# Amplifier_1.net
KiCad netlist of a schematic drawn in Altium Designer
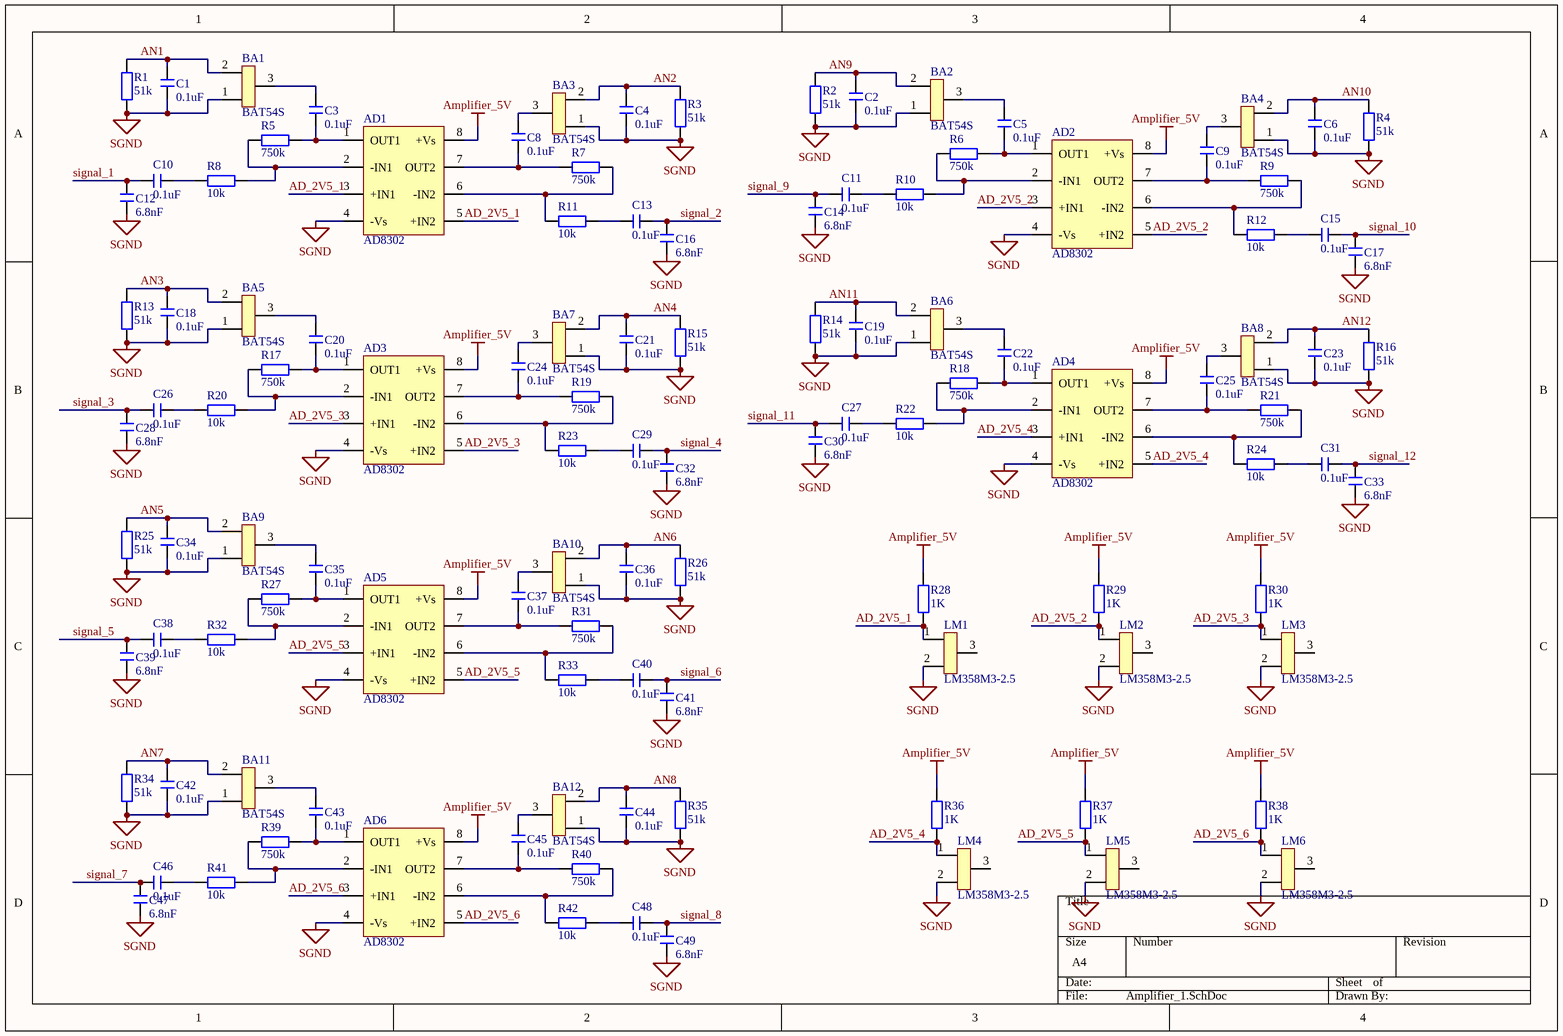
[diagram p0: Amplifier_1.SchDoc]

(export (version "E")
  (design (tool "Eeschema 10.0.6"))
  (components
    (comp (ref "AD1") (value "AD8302") (footprint "SOIC-8") (libsource (lib "运放PCB原理图库") (part "AD8302")))
    (comp (ref "AD2") (value "AD8302") (footprint "SOIC-8") (libsource (lib "运放PCB原理图库") (part "AD8302")))
    (comp (ref "AD3") (value "AD8302") (footprint "SOIC-8") (libsource (lib "运放PCB原理图库") (part "AD8302")))
    (comp (ref "AD4") (value "AD8302") (footprint "SOIC-8") (libsource (lib "运放PCB原理图库") (part "AD8302")))
    (comp (ref "AD5") (value "AD8302") (footprint "SOIC-8") (libsource (lib "运放PCB原理图库") (part "AD8302")))
    (comp (ref "AD6") (value "AD8302") (footprint "SOIC-8") (libsource (lib "运放PCB原理图库") (part "AD8302")))
    (comp (ref "BA1") (value "BAT54S") (footprint "SOT23") (libsource (lib "运放PCB原理图库") (part "BAT54S")))
    (comp (ref "BA2") (value "BAT54S") (footprint "SOT23") (libsource (lib "运放PCB原理图库") (part "BAT54S")))
    (comp (ref "BA3") (value "BAT54S") (footprint "SOT23") (libsource (lib "") (part "BAT54S_1")))
    (comp (ref "BA4") (value "BAT54S") (footprint "SOT23") (libsource (lib "") (part "BAT54S_1")))
    (comp (ref "BA5") (value "BAT54S") (footprint "SOT23") (libsource (lib "运放PCB原理图库") (part "BAT54S")))
    (comp (ref "BA6") (value "BAT54S") (footprint "SOT23") (libsource (lib "运放PCB原理图库") (part "BAT54S")))
    (comp (ref "BA7") (value "BAT54S") (footprint "SOT23") (libsource (lib "") (part "BAT54S_1")))
    (comp (ref "BA8") (value "BAT54S") (footprint "SOT23") (libsource (lib "") (part "BAT54S_1")))
    (comp (ref "BA9") (value "BAT54S") (footprint "SOT23") (libsource (lib "运放PCB原理图库") (part "BAT54S")))
    (comp (ref "BA10") (value "BAT54S") (footprint "SOT23") (libsource (lib "") (part "BAT54S_1")))
    (comp (ref "BA11") (value "BAT54S") (footprint "SOT23") (libsource (lib "运放PCB原理图库") (part "BAT54S")))
    (comp (ref "BA12") (value "BAT54S") (footprint "SOT23") (libsource (lib "") (part "BAT54S_1")))
    (comp (ref "C1")
      (value "0.1uF")
      (footprint "C 0603_L")
      (description "贴片电容")
      (libsource (lib "0.1 - 电阻-电容-电感") (part "C"))
    )
    (comp (ref "C2")
      (value "0.1uF")
      (footprint "C 0603_L")
      (description "贴片电容")
      (libsource (lib "0.1 - 电阻-电容-电感") (part "C"))
    )
    (comp (ref "C3")
      (value "0.1uF")
      (footprint "C 0603_L")
      (description "贴片电容")
      (libsource (lib "0.1 - 电阻-电容-电感") (part "C"))
    )
    (comp (ref "C4")
      (value "0.1uF")
      (footprint "C 0603_L")
      (description "贴片电容")
      (libsource (lib "0.1 - 电阻-电容-电感") (part "C"))
    )
    (comp (ref "C5")
      (value "0.1uF")
      (footprint "C 0603_L")
      (description "贴片电容")
      (libsource (lib "0.1 - 电阻-电容-电感") (part "C"))
    )
    (comp (ref "C6")
      (value "0.1uF")
      (footprint "C 0603_L")
      (description "贴片电容")
      (libsource (lib "0.1 - 电阻-电容-电感") (part "C"))
    )
    (comp (ref "C8")
      (value "0.1uF")
      (footprint "C 0603_L")
      (description "贴片电容")
      (libsource (lib "0.1 - 电阻-电容-电感") (part "C"))
    )
    (comp (ref "C9")
      (value "0.1uF")
      (footprint "C 0603_L")
      (description "贴片电容")
      (libsource (lib "0.1 - 电阻-电容-电感") (part "C"))
    )
    (comp (ref "C10")
      (value "0.1uF")
      (footprint "C 0603_L")
      (description "贴片电容")
      (libsource (lib "0.1 - 电阻-电容-电感") (part "C"))
    )
    (comp (ref "C11")
      (value "0.1uF")
      (footprint "C 0603_L")
      (description "贴片电容")
      (libsource (lib "0.1 - 电阻-电容-电感") (part "C"))
    )
    (comp (ref "C12")
      (value "6.8nF")
      (footprint "C 0805_L")
      (description "贴片电容")
      (libsource (lib "0.1 - 电阻-电容-电感") (part "C"))
    )
    (comp (ref "C13")
      (value "0.1uF")
      (footprint "C 0603_L")
      (description "贴片电容")
      (libsource (lib "0.1 - 电阻-电容-电感") (part "C"))
    )
    (comp (ref "C14")
      (value "6.8nF")
      (footprint "C 0805_L")
      (description "贴片电容")
      (libsource (lib "0.1 - 电阻-电容-电感") (part "C"))
    )
    (comp (ref "C15")
      (value "0.1uF")
      (footprint "C 0603_L")
      (description "贴片电容")
      (libsource (lib "0.1 - 电阻-电容-电感") (part "C"))
    )
    (comp (ref "C16")
      (value "6.8nF")
      (footprint "C 0805_L")
      (description "贴片电容")
      (libsource (lib "0.1 - 电阻-电容-电感") (part "C"))
    )
    (comp (ref "C17")
      (value "6.8nF")
      (footprint "C 0805_L")
      (description "贴片电容")
      (libsource (lib "0.1 - 电阻-电容-电感") (part "C"))
    )
    (comp (ref "C18")
      (value "0.1uF")
      (footprint "C 0603_L")
      (description "贴片电容")
      (libsource (lib "0.1 - 电阻-电容-电感") (part "C"))
    )
    (comp (ref "C19")
      (value "0.1uF")
      (footprint "C 0603_L")
      (description "贴片电容")
      (libsource (lib "0.1 - 电阻-电容-电感") (part "C"))
    )
    (comp (ref "C20")
      (value "0.1uF")
      (footprint "C 0603_L")
      (description "贴片电容")
      (libsource (lib "0.1 - 电阻-电容-电感") (part "C"))
    )
    (comp (ref "C21")
      (value "0.1uF")
      (footprint "C 0603_L")
      (description "贴片电容")
      (libsource (lib "0.1 - 电阻-电容-电感") (part "C"))
    )
    (comp (ref "C22")
      (value "0.1uF")
      (footprint "C 0603_L")
      (description "贴片电容")
      (libsource (lib "0.1 - 电阻-电容-电感") (part "C"))
    )
    (comp (ref "C23")
      (value "0.1uF")
      (footprint "C 0603_L")
      (description "贴片电容")
      (libsource (lib "0.1 - 电阻-电容-电感") (part "C"))
    )
    (comp (ref "C24")
      (value "0.1uF")
      (footprint "C 0603_L")
      (description "贴片电容")
      (libsource (lib "0.1 - 电阻-电容-电感") (part "C"))
    )
    (comp (ref "C25")
      (value "0.1uF")
      (footprint "C 0603_L")
      (description "贴片电容")
      (libsource (lib "0.1 - 电阻-电容-电感") (part "C"))
    )
    (comp (ref "C26")
      (value "0.1uF")
      (footprint "C 0603_L")
      (description "贴片电容")
      (libsource (lib "0.1 - 电阻-电容-电感") (part "C"))
    )
    (comp (ref "C27")
      (value "0.1uF")
      (footprint "C 0603_L")
      (description "贴片电容")
      (libsource (lib "0.1 - 电阻-电容-电感") (part "C"))
    )
    (comp (ref "C28")
      (value "6.8nF")
      (footprint "C 0805_L")
      (description "贴片电容")
      (libsource (lib "0.1 - 电阻-电容-电感") (part "C"))
    )
    (comp (ref "C29")
      (value "0.1uF")
      (footprint "C 0603_L")
      (description "贴片电容")
      (libsource (lib "0.1 - 电阻-电容-电感") (part "C"))
    )
    (comp (ref "C30")
      (value "6.8nF")
      (footprint "C 0805_L")
      (description "贴片电容")
      (libsource (lib "0.1 - 电阻-电容-电感") (part "C"))
    )
    (comp (ref "C31")
      (value "0.1uF")
      (footprint "C 0603_L")
      (description "贴片电容")
      (libsource (lib "0.1 - 电阻-电容-电感") (part "C"))
    )
    (comp (ref "C32")
      (value "6.8nF")
      (footprint "C 0805_L")
      (description "贴片电容")
      (libsource (lib "0.1 - 电阻-电容-电感") (part "C"))
    )
    (comp (ref "C33")
      (value "6.8nF")
      (footprint "C 0805_L")
      (description "贴片电容")
      (libsource (lib "0.1 - 电阻-电容-电感") (part "C"))
    )
    (comp (ref "C34")
      (value "0.1uF")
      (footprint "C 0603_L")
      (description "贴片电容")
      (libsource (lib "0.1 - 电阻-电容-电感") (part "C"))
    )
    (comp (ref "C35")
      (value "0.1uF")
      (footprint "C 0603_L")
      (description "贴片电容")
      (libsource (lib "0.1 - 电阻-电容-电感") (part "C"))
    )
    (comp (ref "C36")
      (value "0.1uF")
      (footprint "C 0603_L")
      (description "贴片电容")
      (libsource (lib "0.1 - 电阻-电容-电感") (part "C"))
    )
    (comp (ref "C37")
      (value "0.1uF")
      (footprint "C 0603_L")
      (description "贴片电容")
      (libsource (lib "0.1 - 电阻-电容-电感") (part "C"))
    )
    (comp (ref "C38")
      (value "0.1uF")
      (footprint "C 0603_L")
      (description "贴片电容")
      (libsource (lib "0.1 - 电阻-电容-电感") (part "C"))
    )
    (comp (ref "C39")
      (value "6.8nF")
      (footprint "C 0805_L")
      (description "贴片电容")
      (libsource (lib "0.1 - 电阻-电容-电感") (part "C"))
    )
    (comp (ref "C40")
      (value "0.1uF")
      (footprint "C 0603_L")
      (description "贴片电容")
      (libsource (lib "0.1 - 电阻-电容-电感") (part "C"))
    )
    (comp (ref "C41")
      (value "6.8nF")
      (footprint "C 0805_L")
      (description "贴片电容")
      (libsource (lib "0.1 - 电阻-电容-电感") (part "C"))
    )
    (comp (ref "C42")
      (value "0.1uF")
      (footprint "C 0603_L")
      (description "贴片电容")
      (libsource (lib "0.1 - 电阻-电容-电感") (part "C"))
    )
    (comp (ref "C43")
      (value "0.1uF")
      (footprint "C 0603_L")
      (description "贴片电容")
      (libsource (lib "0.1 - 电阻-电容-电感") (part "C"))
    )
    (comp (ref "C44")
      (value "0.1uF")
      (footprint "C 0603_L")
      (description "贴片电容")
      (libsource (lib "0.1 - 电阻-电容-电感") (part "C"))
    )
    (comp (ref "C45")
      (value "0.1uF")
      (footprint "C 0603_L")
      (description "贴片电容")
      (libsource (lib "0.1 - 电阻-电容-电感") (part "C"))
    )
    (comp (ref "C46")
      (value "0.1uF")
      (footprint "C 0603_L")
      (description "贴片电容")
      (libsource (lib "0.1 - 电阻-电容-电感") (part "C"))
    )
    (comp (ref "C47")
      (value "6.8nF")
      (footprint "C 0805_L")
      (description "贴片电容")
      (libsource (lib "0.1 - 电阻-电容-电感") (part "C"))
    )
    (comp (ref "C48")
      (value "0.1uF")
      (footprint "C 0603_L")
      (description "贴片电容")
      (libsource (lib "0.1 - 电阻-电容-电感") (part "C"))
    )
    (comp (ref "C49")
      (value "6.8nF")
      (footprint "C 0805_L")
      (description "贴片电容")
      (libsource (lib "0.1 - 电阻-电容-电感") (part "C"))
    )
    (comp (ref "LM1")
      (value "LM358M3-2.5")
      (footprint "SOT23")
      (libsource (lib "运放PCB原理图库") (part "LM358M3-2.5"))
    )
    (comp (ref "LM2")
      (value "LM358M3-2.5")
      (footprint "SOT23")
      (libsource (lib "运放PCB原理图库") (part "LM358M3-2.5"))
    )
    (comp (ref "LM3")
      (value "LM358M3-2.5")
      (footprint "SOT23")
      (libsource (lib "运放PCB原理图库") (part "LM358M3-2.5"))
    )
    (comp (ref "LM4")
      (value "LM358M3-2.5")
      (footprint "SOT23")
      (libsource (lib "运放PCB原理图库") (part "LM358M3-2.5"))
    )
    (comp (ref "LM5")
      (value "LM358M3-2.5")
      (footprint "SOT23")
      (libsource (lib "运放PCB原理图库") (part "LM358M3-2.5"))
    )
    (comp (ref "LM6")
      (value "LM358M3-2.5")
      (footprint "SOT23")
      (libsource (lib "运放PCB原理图库") (part "LM358M3-2.5"))
    )
    (comp (ref "R1")
      (value "51k")
      (footprint "R 0603_L")
      (description "贴片电阻")
      (libsource (lib "0.1 - 电阻-电容-电感") (part "R"))
    )
    (comp (ref "R2")
      (value "51k")
      (footprint "R 0603_L")
      (description "贴片电阻")
      (libsource (lib "0.1 - 电阻-电容-电感") (part "R"))
    )
    (comp (ref "R3")
      (value "51k")
      (footprint "R 0603_L")
      (description "贴片电阻")
      (libsource (lib "0.1 - 电阻-电容-电感") (part "R"))
    )
    (comp (ref "R4")
      (value "51k")
      (footprint "R 0603_L")
      (description "贴片电阻")
      (libsource (lib "0.1 - 电阻-电容-电感") (part "R"))
    )
    (comp (ref "R5")
      (value "750k")
      (footprint "R 0603_L")
      (description "贴片电阻")
      (libsource (lib "0.1 - 电阻-电容-电感") (part "R"))
    )
    (comp (ref "R6")
      (value "750k")
      (footprint "R 0603_L")
      (description "贴片电阻")
      (libsource (lib "0.1 - 电阻-电容-电感") (part "R"))
    )
    (comp (ref "R7")
      (value "750k")
      (footprint "R 0603_L")
      (description "贴片电阻")
      (libsource (lib "0.1 - 电阻-电容-电感") (part "R"))
    )
    (comp (ref "R8")
      (value "10k")
      (footprint "R 0603_L")
      (description "贴片电阻")
      (libsource (lib "0.1 - 电阻-电容-电感") (part "R"))
    )
    (comp (ref "R9")
      (value "750k")
      (footprint "R 0603_L")
      (description "贴片电阻")
      (libsource (lib "0.1 - 电阻-电容-电感") (part "R"))
    )
    (comp (ref "R10")
      (value "10k")
      (footprint "R 0603_L")
      (description "贴片电阻")
      (libsource (lib "0.1 - 电阻-电容-电感") (part "R"))
    )
    (comp (ref "R11")
      (value "10k")
      (footprint "R 0603_L")
      (description "贴片电阻")
      (libsource (lib "0.1 - 电阻-电容-电感") (part "R"))
    )
    (comp (ref "R12")
      (value "10k")
      (footprint "R 0603_L")
      (description "贴片电阻")
      (libsource (lib "0.1 - 电阻-电容-电感") (part "R"))
    )
    (comp (ref "R13")
      (value "51k")
      (footprint "R 0603_L")
      (description "贴片电阻")
      (libsource (lib "0.1 - 电阻-电容-电感") (part "R"))
    )
    (comp (ref "R14")
      (value "51k")
      (footprint "R 0603_L")
      (description "贴片电阻")
      (libsource (lib "0.1 - 电阻-电容-电感") (part "R"))
    )
    (comp (ref "R15")
      (value "51k")
      (footprint "R 0603_L")
      (description "贴片电阻")
      (libsource (lib "0.1 - 电阻-电容-电感") (part "R"))
    )
    (comp (ref "R16")
      (value "51k")
      (footprint "R 0603_L")
      (description "贴片电阻")
      (libsource (lib "0.1 - 电阻-电容-电感") (part "R"))
    )
    (comp (ref "R17")
      (value "750k")
      (footprint "R 0603_L")
      (description "贴片电阻")
      (libsource (lib "0.1 - 电阻-电容-电感") (part "R"))
    )
    (comp (ref "R18")
      (value "750k")
      (footprint "R 0603_L")
      (description "贴片电阻")
      (libsource (lib "0.1 - 电阻-电容-电感") (part "R"))
    )
    (comp (ref "R19")
      (value "750k")
      (footprint "R 0603_L")
      (description "贴片电阻")
      (libsource (lib "0.1 - 电阻-电容-电感") (part "R"))
    )
    (comp (ref "R20")
      (value "10k")
      (footprint "R 0603_L")
      (description "贴片电阻")
      (libsource (lib "0.1 - 电阻-电容-电感") (part "R"))
    )
    (comp (ref "R21")
      (value "750k")
      (footprint "R 0603_L")
      (description "贴片电阻")
      (libsource (lib "0.1 - 电阻-电容-电感") (part "R"))
    )
    (comp (ref "R22")
      (value "10k")
      (footprint "R 0603_L")
      (description "贴片电阻")
      (libsource (lib "0.1 - 电阻-电容-电感") (part "R"))
    )
    (comp (ref "R23")
      (value "10k")
      (footprint "R 0603_L")
      (description "贴片电阻")
      (libsource (lib "0.1 - 电阻-电容-电感") (part "R"))
    )
    (comp (ref "R24")
      (value "10k")
      (footprint "R 0603_L")
      (description "贴片电阻")
      (libsource (lib "0.1 - 电阻-电容-电感") (part "R"))
    )
    (comp (ref "R25")
      (value "51k")
      (footprint "R 0603_L")
      (description "贴片电阻")
      (libsource (lib "0.1 - 电阻-电容-电感") (part "R"))
    )
    (comp (ref "R26")
      (value "51k")
      (footprint "R 0603_L")
      (description "贴片电阻")
      (libsource (lib "0.1 - 电阻-电容-电感") (part "R"))
    )
    (comp (ref "R27")
      (value "750k")
      (footprint "R 0603_L")
      (description "贴片电阻")
      (libsource (lib "0.1 - 电阻-电容-电感") (part "R"))
    )
    (comp (ref "R28")
      (value "1K")
      (footprint "R 0603_L")
      (description "贴片电阻")
      (libsource (lib "0.1 - 电阻-电容-电感") (part "R"))
    )
    (comp (ref "R29")
      (value "1K")
      (footprint "R 0603_L")
      (description "贴片电阻")
      (libsource (lib "0.1 - 电阻-电容-电感") (part "R"))
    )
    (comp (ref "R30")
      (value "1K")
      (footprint "R 0603_L")
      (description "贴片电阻")
      (libsource (lib "0.1 - 电阻-电容-电感") (part "R"))
    )
    (comp (ref "R31")
      (value "750k")
      (footprint "R 0603_L")
      (description "贴片电阻")
      (libsource (lib "0.1 - 电阻-电容-电感") (part "R"))
    )
    (comp (ref "R32")
      (value "10k")
      (footprint "R 0603_L")
      (description "贴片电阻")
      (libsource (lib "0.1 - 电阻-电容-电感") (part "R"))
    )
    (comp (ref "R33")
      (value "10k")
      (footprint "R 0603_L")
      (description "贴片电阻")
      (libsource (lib "0.1 - 电阻-电容-电感") (part "R"))
    )
    (comp (ref "R34")
      (value "51k")
      (footprint "R 0603_L")
      (description "贴片电阻")
      (libsource (lib "0.1 - 电阻-电容-电感") (part "R"))
    )
    (comp (ref "R35")
      (value "51k")
      (footprint "R 0603_L")
      (description "贴片电阻")
      (libsource (lib "0.1 - 电阻-电容-电感") (part "R"))
    )
    (comp (ref "R36")
      (value "1K")
      (footprint "R 0603_L")
      (description "贴片电阻")
      (libsource (lib "0.1 - 电阻-电容-电感") (part "R"))
    )
    (comp (ref "R37")
      (value "1K")
      (footprint "R 0603_L")
      (description "贴片电阻")
      (libsource (lib "0.1 - 电阻-电容-电感") (part "R"))
    )
    (comp (ref "R38")
      (value "1K")
      (footprint "R 0603_L")
      (description "贴片电阻")
      (libsource (lib "0.1 - 电阻-电容-电感") (part "R"))
    )
    (comp (ref "R39")
      (value "750k")
      (footprint "R 0603_L")
      (description "贴片电阻")
      (libsource (lib "0.1 - 电阻-电容-电感") (part "R"))
    )
    (comp (ref "R40")
      (value "750k")
      (footprint "R 0603_L")
      (description "贴片电阻")
      (libsource (lib "0.1 - 电阻-电容-电感") (part "R"))
    )
    (comp (ref "R41")
      (value "10k")
      (footprint "R 0603_L")
      (description "贴片电阻")
      (libsource (lib "0.1 - 电阻-电容-电感") (part "R"))
    )
    (comp (ref "R42")
      (value "10k")
      (footprint "R 0603_L")
      (description "贴片电阻")
      (libsource (lib "0.1 - 电阻-电容-电感") (part "R"))
    )
  )
  (nets
    (net (code "1") (name "/AD_2V5_1") (class "Default")
      (node (ref "AD1") (pin "3") (pinfunction "+IN1_3") (pintype "passive"))
      (node (ref "AD1") (pin "5") (pinfunction "+IN2_5") (pintype "passive"))
      (node (ref "LM1") (pin "1") (pintype "passive"))
      (node (ref "R28") (pin "2") (pinfunction "2_2") (pintype "passive"))
    )
    (net (code "2") (name "/AD_2V5_2") (class "Default")
      (node (ref "AD2") (pin "3") (pinfunction "+IN1_3") (pintype "passive"))
      (node (ref "AD2") (pin "5") (pinfunction "+IN2_5") (pintype "passive"))
      (node (ref "LM2") (pin "1") (pintype "passive"))
      (node (ref "R29") (pin "2") (pinfunction "2_2") (pintype "passive"))
    )
    (net (code "3") (name "/AD_2V5_3") (class "Default")
      (node (ref "AD3") (pin "3") (pinfunction "+IN1_3") (pintype "passive"))
      (node (ref "AD3") (pin "5") (pinfunction "+IN2_5") (pintype "passive"))
      (node (ref "LM3") (pin "1") (pintype "passive"))
      (node (ref "R30") (pin "2") (pinfunction "2_2") (pintype "passive"))
    )
    (net (code "4") (name "/AD_2V5_4") (class "Default")
      (node (ref "AD4") (pin "3") (pinfunction "+IN1_3") (pintype "passive"))
      (node (ref "AD4") (pin "5") (pinfunction "+IN2_5") (pintype "passive"))
      (node (ref "LM4") (pin "1") (pintype "passive"))
      (node (ref "R36") (pin "2") (pinfunction "2_2") (pintype "passive"))
    )
    (net (code "5") (name "/AD_2V5_5") (class "Default")
      (node (ref "AD5") (pin "3") (pinfunction "+IN1_3") (pintype "passive"))
      (node (ref "AD5") (pin "5") (pinfunction "+IN2_5") (pintype "passive"))
      (node (ref "LM5") (pin "1") (pintype "passive"))
      (node (ref "R37") (pin "2") (pinfunction "2_2") (pintype "passive"))
    )
    (net (code "6") (name "/AD_2V5_6") (class "Default")
      (node (ref "AD6") (pin "3") (pinfunction "+IN1_3") (pintype "passive"))
      (node (ref "AD6") (pin "5") (pinfunction "+IN2_5") (pintype "passive"))
      (node (ref "LM6") (pin "1") (pintype "passive"))
      (node (ref "R38") (pin "2") (pinfunction "2_2") (pintype "passive"))
    )
    (net (code "7") (name "/AN1") (class "Default")
      (node (ref "BA1") (pin "2") (pintype "passive"))
      (node (ref "C1") (pin "2") (pinfunction "2_2") (pintype "passive"))
      (node (ref "R1") (pin "2") (pinfunction "2_2") (pintype "passive"))
    )
    (net (code "8") (name "/AN2") (class "Default")
      (node (ref "BA3") (pin "2") (pintype "passive"))
      (node (ref "C4") (pin "2") (pinfunction "2_2") (pintype "passive"))
      (node (ref "R3") (pin "2") (pinfunction "2_2") (pintype "passive"))
    )
    (net (code "9") (name "/AN3") (class "Default")
      (node (ref "BA5") (pin "2") (pintype "passive"))
      (node (ref "C18") (pin "2") (pinfunction "2_2") (pintype "passive"))
      (node (ref "R13") (pin "2") (pinfunction "2_2") (pintype "passive"))
    )
    (net (code "10") (name "/AN4") (class "Default")
      (node (ref "BA7") (pin "2") (pintype "passive"))
      (node (ref "C21") (pin "2") (pinfunction "2_2") (pintype "passive"))
      (node (ref "R15") (pin "2") (pinfunction "2_2") (pintype "passive"))
    )
    (net (code "11") (name "/AN5") (class "Default")
      (node (ref "BA9") (pin "2") (pintype "passive"))
      (node (ref "C34") (pin "2") (pinfunction "2_2") (pintype "passive"))
      (node (ref "R25") (pin "2") (pinfunction "2_2") (pintype "passive"))
    )
    (net (code "12") (name "/AN6") (class "Default")
      (node (ref "BA10") (pin "2") (pintype "passive"))
      (node (ref "C36") (pin "2") (pinfunction "2_2") (pintype "passive"))
      (node (ref "R26") (pin "2") (pinfunction "2_2") (pintype "passive"))
    )
    (net (code "13") (name "/AN7") (class "Default")
      (node (ref "BA11") (pin "2") (pintype "passive"))
      (node (ref "C42") (pin "2") (pinfunction "2_2") (pintype "passive"))
      (node (ref "R34") (pin "2") (pinfunction "2_2") (pintype "passive"))
    )
    (net (code "14") (name "/AN8") (class "Default")
      (node (ref "BA12") (pin "2") (pintype "passive"))
      (node (ref "C44") (pin "2") (pinfunction "2_2") (pintype "passive"))
      (node (ref "R35") (pin "2") (pinfunction "2_2") (pintype "passive"))
    )
    (net (code "15") (name "/AN9") (class "Default")
      (node (ref "BA2") (pin "2") (pintype "passive"))
      (node (ref "C2") (pin "2") (pinfunction "2_2") (pintype "passive"))
      (node (ref "R2") (pin "2") (pinfunction "2_2") (pintype "passive"))
    )
    (net (code "16") (name "/AN10") (class "Default")
      (node (ref "BA4") (pin "2") (pintype "passive"))
      (node (ref "C6") (pin "2") (pinfunction "2_2") (pintype "passive"))
      (node (ref "R4") (pin "2") (pinfunction "2_2") (pintype "passive"))
    )
    (net (code "17") (name "/AN11") (class "Default")
      (node (ref "BA6") (pin "2") (pintype "passive"))
      (node (ref "C19") (pin "2") (pinfunction "2_2") (pintype "passive"))
      (node (ref "R14") (pin "2") (pinfunction "2_2") (pintype "passive"))
    )
    (net (code "18") (name "/AN12") (class "Default")
      (node (ref "BA8") (pin "2") (pintype "passive"))
      (node (ref "C23") (pin "2") (pinfunction "2_2") (pintype "passive"))
      (node (ref "R16") (pin "2") (pinfunction "2_2") (pintype "passive"))
    )
    (net (code "19") (name "/signal_1") (class "Default")
      (node (ref "C10") (pin "1") (pinfunction "1_1") (pintype "passive"))
      (node (ref "C12") (pin "2") (pinfunction "2_2") (pintype "passive"))
    )
    (net (code "20") (name "/signal_2") (class "Default")
      (node (ref "C13") (pin "2") (pinfunction "2_2") (pintype "passive"))
      (node (ref "C16") (pin "2") (pinfunction "2_2") (pintype "passive"))
    )
    (net (code "21") (name "/signal_3") (class "Default")
      (node (ref "C26") (pin "1") (pinfunction "1_1") (pintype "passive"))
      (node (ref "C28") (pin "2") (pinfunction "2_2") (pintype "passive"))
    )
    (net (code "22") (name "/signal_4") (class "Default")
      (node (ref "C29") (pin "2") (pinfunction "2_2") (pintype "passive"))
      (node (ref "C32") (pin "2") (pinfunction "2_2") (pintype "passive"))
    )
    (net (code "23") (name "/signal_5") (class "Default")
      (node (ref "C38") (pin "1") (pinfunction "1_1") (pintype "passive"))
      (node (ref "C39") (pin "2") (pinfunction "2_2") (pintype "passive"))
    )
    (net (code "24") (name "/signal_6") (class "Default")
      (node (ref "C40") (pin "2") (pinfunction "2_2") (pintype "passive"))
      (node (ref "C41") (pin "2") (pinfunction "2_2") (pintype "passive"))
    )
    (net (code "25") (name "/signal_7") (class "Default")
      (node (ref "C46") (pin "1") (pinfunction "1_1") (pintype "passive"))
      (node (ref "C47") (pin "2") (pinfunction "2_2") (pintype "passive"))
    )
    (net (code "26") (name "/signal_8") (class "Default")
      (node (ref "C48") (pin "2") (pinfunction "2_2") (pintype "passive"))
      (node (ref "C49") (pin "2") (pinfunction "2_2") (pintype "passive"))
    )
    (net (code "27") (name "/signal_9") (class "Default")
      (node (ref "C11") (pin "1") (pinfunction "1_1") (pintype "passive"))
      (node (ref "C14") (pin "2") (pinfunction "2_2") (pintype "passive"))
    )
    (net (code "28") (name "/signal_10") (class "Default")
      (node (ref "C15") (pin "2") (pinfunction "2_2") (pintype "passive"))
      (node (ref "C17") (pin "2") (pinfunction "2_2") (pintype "passive"))
    )
    (net (code "29") (name "/signal_11") (class "Default")
      (node (ref "C27") (pin "1") (pinfunction "1_1") (pintype "passive"))
      (node (ref "C30") (pin "2") (pinfunction "2_2") (pintype "passive"))
    )
    (net (code "30") (name "/signal_12") (class "Default")
      (node (ref "C31") (pin "2") (pinfunction "2_2") (pintype "passive"))
      (node (ref "C33") (pin "2") (pinfunction "2_2") (pintype "passive"))
    )
    (net (code "31") (name "Amplifier_5V") (class "Default")
      (node (ref "AD1") (pin "8") (pinfunction "+Vs_8") (pintype "passive"))
      (node (ref "AD2") (pin "8") (pinfunction "+Vs_8") (pintype "passive"))
      (node (ref "AD3") (pin "8") (pinfunction "+Vs_8") (pintype "passive"))
      (node (ref "AD4") (pin "8") (pinfunction "+Vs_8") (pintype "passive"))
      (node (ref "AD5") (pin "8") (pinfunction "+Vs_8") (pintype "passive"))
      (node (ref "AD6") (pin "8") (pinfunction "+Vs_8") (pintype "passive"))
      (node (ref "R28") (pin "1") (pinfunction "1_1") (pintype "passive"))
      (node (ref "R29") (pin "1") (pinfunction "1_1") (pintype "passive"))
      (node (ref "R30") (pin "1") (pinfunction "1_1") (pintype "passive"))
      (node (ref "R36") (pin "1") (pinfunction "1_1") (pintype "passive"))
      (node (ref "R37") (pin "1") (pinfunction "1_1") (pintype "passive"))
      (node (ref "R38") (pin "1") (pinfunction "1_1") (pintype "passive"))
    )
    (net (code "32") (name "Net-(AD1--IN1)") (class "Default")
      (node (ref "AD1") (pin "2") (pinfunction "-IN1_2") (pintype "passive"))
      (node (ref "R5") (pin "1") (pinfunction "1_1") (pintype "passive"))
      (node (ref "R8") (pin "2") (pinfunction "2_2") (pintype "passive"))
    )
    (net (code "33") (name "Net-(AD1--IN2)") (class "Default")
      (node (ref "AD1") (pin "6") (pinfunction "-IN2_6") (pintype "passive"))
      (node (ref "R11") (pin "1") (pinfunction "1_1") (pintype "passive"))
      (node (ref "R7") (pin "2") (pinfunction "2_2") (pintype "passive"))
    )
    (net (code "34") (name "Net-(AD1-OUT1)") (class "Default")
      (node (ref "AD1") (pin "1") (pinfunction "OUT1_1") (pintype "passive"))
      (node (ref "C3") (pin "1") (pinfunction "1_1") (pintype "passive"))
      (node (ref "R5") (pin "2") (pinfunction "2_2") (pintype "passive"))
    )
    (net (code "35") (name "Net-(AD1-OUT2)") (class "Default")
      (node (ref "AD1") (pin "7") (pinfunction "OUT2_7") (pintype "passive"))
      (node (ref "C8") (pin "1") (pinfunction "1_1") (pintype "passive"))
      (node (ref "R7") (pin "1") (pinfunction "1_1") (pintype "passive"))
    )
    (net (code "36") (name "Net-(AD2--IN1)") (class "Default")
      (node (ref "AD2") (pin "2") (pinfunction "-IN1_2") (pintype "passive"))
      (node (ref "R10") (pin "2") (pinfunction "2_2") (pintype "passive"))
      (node (ref "R6") (pin "1") (pinfunction "1_1") (pintype "passive"))
    )
    (net (code "37") (name "Net-(AD2--IN2)") (class "Default")
      (node (ref "AD2") (pin "6") (pinfunction "-IN2_6") (pintype "passive"))
      (node (ref "R12") (pin "1") (pinfunction "1_1") (pintype "passive"))
      (node (ref "R9") (pin "2") (pinfunction "2_2") (pintype "passive"))
    )
    (net (code "38") (name "Net-(AD2-OUT1)") (class "Default")
      (node (ref "AD2") (pin "1") (pinfunction "OUT1_1") (pintype "passive"))
      (node (ref "C5") (pin "1") (pinfunction "1_1") (pintype "passive"))
      (node (ref "R6") (pin "2") (pinfunction "2_2") (pintype "passive"))
    )
    (net (code "39") (name "Net-(AD2-OUT2)") (class "Default")
      (node (ref "AD2") (pin "7") (pinfunction "OUT2_7") (pintype "passive"))
      (node (ref "C9") (pin "1") (pinfunction "1_1") (pintype "passive"))
      (node (ref "R9") (pin "1") (pinfunction "1_1") (pintype "passive"))
    )
    (net (code "40") (name "Net-(AD3--IN1)") (class "Default")
      (node (ref "AD3") (pin "2") (pinfunction "-IN1_2") (pintype "passive"))
      (node (ref "R17") (pin "1") (pinfunction "1_1") (pintype "passive"))
      (node (ref "R20") (pin "2") (pinfunction "2_2") (pintype "passive"))
    )
    (net (code "41") (name "Net-(AD3--IN2)") (class "Default")
      (node (ref "AD3") (pin "6") (pinfunction "-IN2_6") (pintype "passive"))
      (node (ref "R19") (pin "2") (pinfunction "2_2") (pintype "passive"))
      (node (ref "R23") (pin "1") (pinfunction "1_1") (pintype "passive"))
    )
    (net (code "42") (name "Net-(AD3-OUT1)") (class "Default")
      (node (ref "AD3") (pin "1") (pinfunction "OUT1_1") (pintype "passive"))
      (node (ref "C20") (pin "1") (pinfunction "1_1") (pintype "passive"))
      (node (ref "R17") (pin "2") (pinfunction "2_2") (pintype "passive"))
    )
    (net (code "43") (name "Net-(AD3-OUT2)") (class "Default")
      (node (ref "AD3") (pin "7") (pinfunction "OUT2_7") (pintype "passive"))
      (node (ref "C24") (pin "1") (pinfunction "1_1") (pintype "passive"))
      (node (ref "R19") (pin "1") (pinfunction "1_1") (pintype "passive"))
    )
    (net (code "44") (name "Net-(AD4--IN1)") (class "Default")
      (node (ref "AD4") (pin "2") (pinfunction "-IN1_2") (pintype "passive"))
      (node (ref "R18") (pin "1") (pinfunction "1_1") (pintype "passive"))
      (node (ref "R22") (pin "2") (pinfunction "2_2") (pintype "passive"))
    )
    (net (code "45") (name "Net-(AD4--IN2)") (class "Default")
      (node (ref "AD4") (pin "6") (pinfunction "-IN2_6") (pintype "passive"))
      (node (ref "R21") (pin "2") (pinfunction "2_2") (pintype "passive"))
      (node (ref "R24") (pin "1") (pinfunction "1_1") (pintype "passive"))
    )
    (net (code "46") (name "Net-(AD4-OUT1)") (class "Default")
      (node (ref "AD4") (pin "1") (pinfunction "OUT1_1") (pintype "passive"))
      (node (ref "C22") (pin "1") (pinfunction "1_1") (pintype "passive"))
      (node (ref "R18") (pin "2") (pinfunction "2_2") (pintype "passive"))
    )
    (net (code "47") (name "Net-(AD4-OUT2)") (class "Default")
      (node (ref "AD4") (pin "7") (pinfunction "OUT2_7") (pintype "passive"))
      (node (ref "C25") (pin "1") (pinfunction "1_1") (pintype "passive"))
      (node (ref "R21") (pin "1") (pinfunction "1_1") (pintype "passive"))
    )
    (net (code "48") (name "Net-(AD5--IN1)") (class "Default")
      (node (ref "AD5") (pin "2") (pinfunction "-IN1_2") (pintype "passive"))
      (node (ref "R27") (pin "1") (pinfunction "1_1") (pintype "passive"))
      (node (ref "R32") (pin "2") (pinfunction "2_2") (pintype "passive"))
    )
    (net (code "49") (name "Net-(AD5--IN2)") (class "Default")
      (node (ref "AD5") (pin "6") (pinfunction "-IN2_6") (pintype "passive"))
      (node (ref "R31") (pin "2") (pinfunction "2_2") (pintype "passive"))
      (node (ref "R33") (pin "1") (pinfunction "1_1") (pintype "passive"))
    )
    (net (code "50") (name "Net-(AD5-OUT1)") (class "Default")
      (node (ref "AD5") (pin "1") (pinfunction "OUT1_1") (pintype "passive"))
      (node (ref "C35") (pin "1") (pinfunction "1_1") (pintype "passive"))
      (node (ref "R27") (pin "2") (pinfunction "2_2") (pintype "passive"))
    )
    (net (code "51") (name "Net-(AD5-OUT2)") (class "Default")
      (node (ref "AD5") (pin "7") (pinfunction "OUT2_7") (pintype "passive"))
      (node (ref "C37") (pin "1") (pinfunction "1_1") (pintype "passive"))
      (node (ref "R31") (pin "1") (pinfunction "1_1") (pintype "passive"))
    )
    (net (code "52") (name "Net-(AD6--IN1)") (class "Default")
      (node (ref "AD6") (pin "2") (pinfunction "-IN1_2") (pintype "passive"))
      (node (ref "R39") (pin "1") (pinfunction "1_1") (pintype "passive"))
      (node (ref "R41") (pin "2") (pinfunction "2_2") (pintype "passive"))
    )
    (net (code "53") (name "Net-(AD6--IN2)") (class "Default")
      (node (ref "AD6") (pin "6") (pinfunction "-IN2_6") (pintype "passive"))
      (node (ref "R40") (pin "2") (pinfunction "2_2") (pintype "passive"))
      (node (ref "R42") (pin "1") (pinfunction "1_1") (pintype "passive"))
    )
    (net (code "54") (name "Net-(AD6-OUT1)") (class "Default")
      (node (ref "AD6") (pin "1") (pinfunction "OUT1_1") (pintype "passive"))
      (node (ref "C43") (pin "1") (pinfunction "1_1") (pintype "passive"))
      (node (ref "R39") (pin "2") (pinfunction "2_2") (pintype "passive"))
    )
    (net (code "55") (name "Net-(AD6-OUT2)") (class "Default")
      (node (ref "AD6") (pin "7") (pinfunction "OUT2_7") (pintype "passive"))
      (node (ref "C45") (pin "1") (pinfunction "1_1") (pintype "passive"))
      (node (ref "R40") (pin "1") (pinfunction "1_1") (pintype "passive"))
    )
    (net (code "56") (name "Net-(BA1-Pad3)") (class "Default")
      (node (ref "BA1") (pin "3") (pintype "passive"))
      (node (ref "C3") (pin "2") (pinfunction "2_2") (pintype "passive"))
    )
    (net (code "57") (name "Net-(BA2-Pad3)") (class "Default")
      (node (ref "BA2") (pin "3") (pintype "passive"))
      (node (ref "C5") (pin "2") (pinfunction "2_2") (pintype "passive"))
    )
    (net (code "58") (name "Net-(BA3-Pad3)") (class "Default")
      (node (ref "BA3") (pin "3") (pintype "passive"))
      (node (ref "C8") (pin "2") (pinfunction "2_2") (pintype "passive"))
    )
    (net (code "59") (name "Net-(BA4-Pad3)") (class "Default")
      (node (ref "BA4") (pin "3") (pintype "passive"))
      (node (ref "C9") (pin "2") (pinfunction "2_2") (pintype "passive"))
    )
    (net (code "60") (name "Net-(BA5-Pad3)") (class "Default")
      (node (ref "BA5") (pin "3") (pintype "passive"))
      (node (ref "C20") (pin "2") (pinfunction "2_2") (pintype "passive"))
    )
    (net (code "61") (name "Net-(BA6-Pad3)") (class "Default")
      (node (ref "BA6") (pin "3") (pintype "passive"))
      (node (ref "C22") (pin "2") (pinfunction "2_2") (pintype "passive"))
    )
    (net (code "62") (name "Net-(BA7-Pad3)") (class "Default")
      (node (ref "BA7") (pin "3") (pintype "passive"))
      (node (ref "C24") (pin "2") (pinfunction "2_2") (pintype "passive"))
    )
    (net (code "63") (name "Net-(BA8-Pad3)") (class "Default")
      (node (ref "BA8") (pin "3") (pintype "passive"))
      (node (ref "C25") (pin "2") (pinfunction "2_2") (pintype "passive"))
    )
    (net (code "64") (name "Net-(BA9-Pad3)") (class "Default")
      (node (ref "BA9") (pin "3") (pintype "passive"))
      (node (ref "C35") (pin "2") (pinfunction "2_2") (pintype "passive"))
    )
    (net (code "65") (name "Net-(BA10-Pad3)") (class "Default")
      (node (ref "BA10") (pin "3") (pintype "passive"))
      (node (ref "C37") (pin "2") (pinfunction "2_2") (pintype "passive"))
    )
    (net (code "66") (name "Net-(BA11-Pad3)") (class "Default")
      (node (ref "BA11") (pin "3") (pintype "passive"))
      (node (ref "C43") (pin "2") (pinfunction "2_2") (pintype "passive"))
    )
    (net (code "67") (name "Net-(BA12-Pad3)") (class "Default")
      (node (ref "BA12") (pin "3") (pintype "passive"))
      (node (ref "C45") (pin "2") (pinfunction "2_2") (pintype "passive"))
    )
    (net (code "68") (name "Net-(C10-Pad2)") (class "Default")
      (node (ref "C10") (pin "2") (pinfunction "2_2") (pintype "passive"))
      (node (ref "R8") (pin "1") (pinfunction "1_1") (pintype "passive"))
    )
    (net (code "69") (name "Net-(C11-Pad2)") (class "Default")
      (node (ref "C11") (pin "2") (pinfunction "2_2") (pintype "passive"))
      (node (ref "R10") (pin "1") (pinfunction "1_1") (pintype "passive"))
    )
    (net (code "70") (name "Net-(C13-Pad1)") (class "Default")
      (node (ref "C13") (pin "1") (pinfunction "1_1") (pintype "passive"))
      (node (ref "R11") (pin "2") (pinfunction "2_2") (pintype "passive"))
    )
    (net (code "71") (name "Net-(C15-Pad1)") (class "Default")
      (node (ref "C15") (pin "1") (pinfunction "1_1") (pintype "passive"))
      (node (ref "R12") (pin "2") (pinfunction "2_2") (pintype "passive"))
    )
    (net (code "72") (name "Net-(C26-Pad2)") (class "Default")
      (node (ref "C26") (pin "2") (pinfunction "2_2") (pintype "passive"))
      (node (ref "R20") (pin "1") (pinfunction "1_1") (pintype "passive"))
    )
    (net (code "73") (name "Net-(C27-Pad2)") (class "Default")
      (node (ref "C27") (pin "2") (pinfunction "2_2") (pintype "passive"))
      (node (ref "R22") (pin "1") (pinfunction "1_1") (pintype "passive"))
    )
    (net (code "74") (name "Net-(C29-Pad1)") (class "Default")
      (node (ref "C29") (pin "1") (pinfunction "1_1") (pintype "passive"))
      (node (ref "R23") (pin "2") (pinfunction "2_2") (pintype "passive"))
    )
    (net (code "75") (name "Net-(C31-Pad1)") (class "Default")
      (node (ref "C31") (pin "1") (pinfunction "1_1") (pintype "passive"))
      (node (ref "R24") (pin "2") (pinfunction "2_2") (pintype "passive"))
    )
    (net (code "76") (name "Net-(C38-Pad2)") (class "Default")
      (node (ref "C38") (pin "2") (pinfunction "2_2") (pintype "passive"))
      (node (ref "R32") (pin "1") (pinfunction "1_1") (pintype "passive"))
    )
    (net (code "77") (name "Net-(C40-Pad1)") (class "Default")
      (node (ref "C40") (pin "1") (pinfunction "1_1") (pintype "passive"))
      (node (ref "R33") (pin "2") (pinfunction "2_2") (pintype "passive"))
    )
    (net (code "78") (name "Net-(C46-Pad2)") (class "Default")
      (node (ref "C46") (pin "2") (pinfunction "2_2") (pintype "passive"))
      (node (ref "R41") (pin "1") (pinfunction "1_1") (pintype "passive"))
    )
    (net (code "79") (name "Net-(C48-Pad1)") (class "Default")
      (node (ref "C48") (pin "1") (pinfunction "1_1") (pintype "passive"))
      (node (ref "R42") (pin "2") (pinfunction "2_2") (pintype "passive"))
    )
    (net (code "80") (name "SGND") (class "Default")
      (node (ref "AD1") (pin "4") (pinfunction "-Vs_4") (pintype "passive"))
      (node (ref "AD2") (pin "4") (pinfunction "-Vs_4") (pintype "passive"))
      (node (ref "AD3") (pin "4") (pinfunction "-Vs_4") (pintype "passive"))
      (node (ref "AD4") (pin "4") (pinfunction "-Vs_4") (pintype "passive"))
      (node (ref "AD5") (pin "4") (pinfunction "-Vs_4") (pintype "passive"))
      (node (ref "AD6") (pin "4") (pinfunction "-Vs_4") (pintype "passive"))
      (node (ref "BA1") (pin "1") (pintype "passive"))
      (node (ref "BA10") (pin "1") (pintype "passive"))
      (node (ref "BA11") (pin "1") (pintype "passive"))
      (node (ref "BA12") (pin "1") (pintype "passive"))
      (node (ref "BA2") (pin "1") (pintype "passive"))
      (node (ref "BA3") (pin "1") (pintype "passive"))
      (node (ref "BA4") (pin "1") (pintype "passive"))
      (node (ref "BA5") (pin "1") (pintype "passive"))
      (node (ref "BA6") (pin "1") (pintype "passive"))
      (node (ref "BA7") (pin "1") (pintype "passive"))
      (node (ref "BA8") (pin "1") (pintype "passive"))
      (node (ref "BA9") (pin "1") (pintype "passive"))
      (node (ref "C1") (pin "1") (pinfunction "1_1") (pintype "passive"))
      (node (ref "C12") (pin "1") (pinfunction "1_1") (pintype "passive"))
      (node (ref "C14") (pin "1") (pinfunction "1_1") (pintype "passive"))
      (node (ref "C16") (pin "1") (pinfunction "1_1") (pintype "passive"))
      (node (ref "C17") (pin "1") (pinfunction "1_1") (pintype "passive"))
      (node (ref "C18") (pin "1") (pinfunction "1_1") (pintype "passive"))
      (node (ref "C19") (pin "1") (pinfunction "1_1") (pintype "passive"))
      (node (ref "C2") (pin "1") (pinfunction "1_1") (pintype "passive"))
      (node (ref "C21") (pin "1") (pinfunction "1_1") (pintype "passive"))
      (node (ref "C23") (pin "1") (pinfunction "1_1") (pintype "passive"))
      (node (ref "C28") (pin "1") (pinfunction "1_1") (pintype "passive"))
      (node (ref "C30") (pin "1") (pinfunction "1_1") (pintype "passive"))
      (node (ref "C32") (pin "1") (pinfunction "1_1") (pintype "passive"))
      (node (ref "C33") (pin "1") (pinfunction "1_1") (pintype "passive"))
      (node (ref "C34") (pin "1") (pinfunction "1_1") (pintype "passive"))
      (node (ref "C36") (pin "1") (pinfunction "1_1") (pintype "passive"))
      (node (ref "C39") (pin "1") (pinfunction "1_1") (pintype "passive"))
      (node (ref "C4") (pin "1") (pinfunction "1_1") (pintype "passive"))
      (node (ref "C41") (pin "1") (pinfunction "1_1") (pintype "passive"))
      (node (ref "C42") (pin "1") (pinfunction "1_1") (pintype "passive"))
      (node (ref "C44") (pin "1") (pinfunction "1_1") (pintype "passive"))
      (node (ref "C47") (pin "1") (pinfunction "1_1") (pintype "passive"))
      (node (ref "C49") (pin "1") (pinfunction "1_1") (pintype "passive"))
      (node (ref "C6") (pin "1") (pinfunction "1_1") (pintype "passive"))
      (node (ref "LM1") (pin "2") (pintype "passive"))
      (node (ref "LM2") (pin "2") (pintype "passive"))
      (node (ref "LM3") (pin "2") (pintype "passive"))
      (node (ref "LM4") (pin "2") (pintype "passive"))
      (node (ref "LM5") (pin "2") (pintype "passive"))
      (node (ref "LM6") (pin "2") (pintype "passive"))
      (node (ref "R1") (pin "1") (pinfunction "1_1") (pintype "passive"))
      (node (ref "R13") (pin "1") (pinfunction "1_1") (pintype "passive"))
      (node (ref "R14") (pin "1") (pinfunction "1_1") (pintype "passive"))
      (node (ref "R15") (pin "1") (pinfunction "1_1") (pintype "passive"))
      (node (ref "R16") (pin "1") (pinfunction "1_1") (pintype "passive"))
      (node (ref "R2") (pin "1") (pinfunction "1_1") (pintype "passive"))
      (node (ref "R25") (pin "1") (pinfunction "1_1") (pintype "passive"))
      (node (ref "R26") (pin "1") (pinfunction "1_1") (pintype "passive"))
      (node (ref "R3") (pin "1") (pinfunction "1_1") (pintype "passive"))
      (node (ref "R34") (pin "1") (pinfunction "1_1") (pintype "passive"))
      (node (ref "R35") (pin "1") (pinfunction "1_1") (pintype "passive"))
      (node (ref "R4") (pin "1") (pinfunction "1_1") (pintype "passive"))
    )
    (net (code "81") (name "unconnected-(LM1-Pad3)") (class "Default")
      (node (ref "LM1") (pin "3") (pintype "passive"))
    )
    (net (code "82") (name "unconnected-(LM2-Pad3)") (class "Default")
      (node (ref "LM2") (pin "3") (pintype "passive"))
    )
    (net (code "83") (name "unconnected-(LM3-Pad3)") (class "Default")
      (node (ref "LM3") (pin "3") (pintype "passive"))
    )
    (net (code "84") (name "unconnected-(LM4-Pad3)") (class "Default")
      (node (ref "LM4") (pin "3") (pintype "passive"))
    )
    (net (code "85") (name "unconnected-(LM5-Pad3)") (class "Default")
      (node (ref "LM5") (pin "3") (pintype "passive"))
    )
    (net (code "86") (name "unconnected-(LM6-Pad3)") (class "Default")
      (node (ref "LM6") (pin "3") (pintype "passive"))
    )
  )
)
